# NearField_H_Probe.net
KiCad netlist of a schematic drawn in Altium Designer
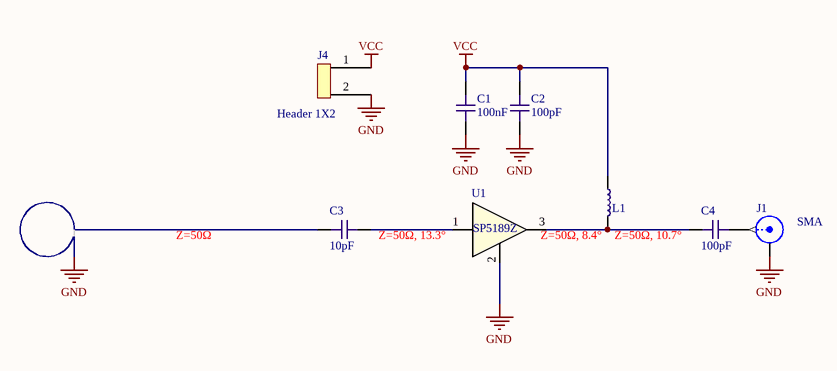
[diagram p0: NearField_H_Probe.SchDoc]

(export (version "E")
  (design (tool "Eeschema 10.0.6"))
  (components
    (comp (ref "C1")
      (value "100nF")
      (footprint "C0402-IPC")
      (description "Chip Capacitor, 0402, 100nF, 10V, X5R")
      (fields (field (name "Comment") "C0402 100nF 10V X5R"))
      (libsource (lib "Capacitors") (part "C0402 100nF 10V X5R"))
    )
    (comp (ref "C2")
      (value "100pF")
      (footprint "C0402-IPC")
      (description "Chip Capacitor, 0402, 100p, 1%, 50V, C0G")
      (fields (field (name "Comment") "C0402 100pF 50V C0G"))
      (libsource (lib "Capacitors") (part "C0402 100pF 50V C0G"))
    )
    (comp (ref "C3")
      (value "10pF")
      (footprint "C0402-IPC")
      (description "Chip Capacitor, 0402, 10pF, 50V, C0G")
      (fields (field (name "Comment") "C0402 10pF 50V C0G"))
      (libsource (lib "Capacitors") (part "C0402 10pF 50V C0G"))
    )
    (comp (ref "C4")
      (value "100pF")
      (footprint "C0402-IPC")
      (description "Chip Capacitor, 0402, 100p, 1%, 50V, C0G")
      (fields (field (name "Comment") "C0402 100pF 50V C0G"))
      (libsource (lib "Capacitors") (part "C0402 100pF 50V C0G"))
    )
    (comp (ref "J1")
      (value "SMA")
      (footprint "SMA Edge Launch (Horizontal)")
      (description "SMA Connector")
      (libsource (lib "Connectors") (part "SMA"))
    )
    (comp (ref "J4")
      (value "Header 1X2")
      (footprint "Header 1x2 TH Pitch 2.54mm")
      (libsource (lib "Connectors") (part "Header 1X2"))
    )
    (comp (ref "L1")
      (value "LQW15AN47NG8ZD")
      (footprint "L0402-Murata-WW-High-Density")
      (description "47nH Unshielded Wirewound Inductor 440mA 648mOhm Max 0402 (1005 Metric)")
      (libsource (lib "Inductors") (part "L0402 47nH High-Q"))
    )
    (comp (ref "U1")
      (value "SP5189Z")
      (footprint "RF Components:SOT-89")
      (description "RF Amplifier .05-4GHz SSG 12.8dB NF .8dB GaAs")
      (libsource (lib "RF Components") (part "SPF5189Z"))
    )
  )
  (nets
    (net (code "1") (name "GND") (class "Default")
      (node (ref "C1") (pin "1") (pintype "passive"))
      (node (ref "C2") (pin "1") (pintype "passive"))
      (node (ref "C3") (pin "1") (pintype "passive"))
      (node (ref "J1") (pin "2") (pinfunction "Y_2") (pintype "power_in"))
      (node (ref "J4") (pin "2") (pintype "passive"))
      (node (ref "U1") (pin "2") (pinfunction "GND_2") (pintype "passive"))
    )
    (net (code "2") (name "Net-(J1-X)") (class "Default")
      (node (ref "C4") (pin "2") (pintype "passive"))
      (node (ref "J1") (pin "1") (pinfunction "X_1") (pintype "output"))
    )
    (net (code "3") (name "Net-(U1-RFIN)") (class "Default")
      (node (ref "C3") (pin "2") (pintype "passive"))
      (node (ref "U1") (pin "1") (pinfunction "RFIN_1") (pintype "passive"))
    )
    (net (code "4") (name "Net-(U1-RFOUT{slash}DCBIAS)") (class "Default")
      (node (ref "C4") (pin "1") (pintype "passive"))
      (node (ref "L1") (pin "2") (pintype "passive"))
      (node (ref "U1") (pin "3") (pinfunction "RFOUT/DCBIAS_3") (pintype "passive"))
    )
    (net (code "5") (name "VCC") (class "Default")
      (node (ref "C1") (pin "2") (pintype "passive"))
      (node (ref "C2") (pin "2") (pintype "passive"))
      (node (ref "J4") (pin "1") (pintype "passive"))
      (node (ref "L1") (pin "1") (pintype "passive"))
    )
  )
)
